# power.net
KiCad netlist of a schematic drawn in Altium Designer
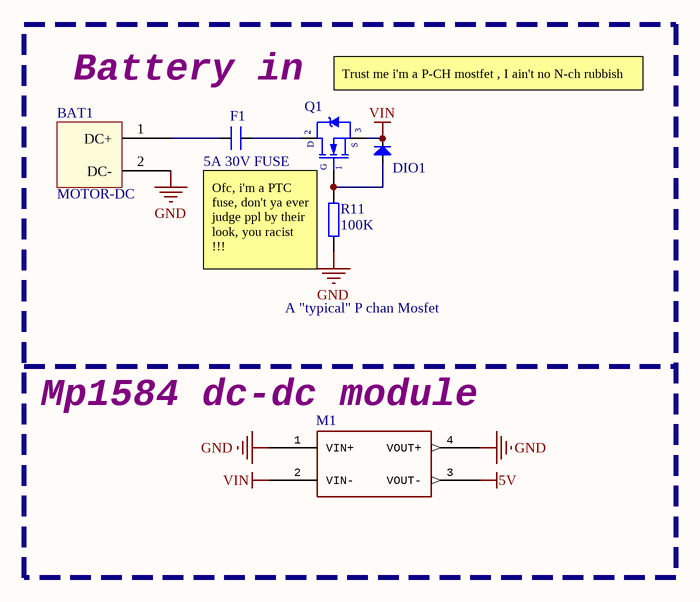
[diagram p0: power.SchDoc]

(export (version "E")
  (design (tool "Eeschema 10.0.6"))
  (components
    (comp (ref "BAT1")
      (value "MOTOR-DC")
      (footprint "CON2-5.08DC")
      (libsource (lib "RASHBERRY_EXTERN") (part "MOTOR-DC"))
    )
    (comp (ref "DIO1")
      (value "Diode SMD")
      (footprint "DIO-SMD-123")
      (description "Default Diode")
      (fields (field (name "PUBLISHER") "Altium Limited"))
      (libsource (lib "My Library") (part "Diode SMD"))
    )
    (comp (ref "F1")
      (value "5A 30V FUSE")
      (footprint "CN2")
      (description "Cap np 104 => 105pF")
      (libsource (lib "My Library") (part "CN2"))
    )
    (comp (ref "M1")
      (value "MP1584-dc-brick-pcb Step down Input: 4.5V - 28V Ouput 0.8V - 25V max. 3A Cheap on ebay")
      (footprint "DC-BRICK")
      (libsource (lib "MP1584-dc-brick") (part "MP1584"))
    )
    (comp (ref "Q1")
      (value "A \"typical\" P chan Mosfet")
      (footprint "QTO-220")
      (description "MOSFET N - CHANNEL 500V - 0.75 - 8A - TO-220")
      (libsource (lib "My Library") (part "IRF840"))
    )
    (comp (ref "R11")
      (value "100K")
      (footprint "SMT0603")
      (description "RES SM 0603 100K")
      (fields (field (name "Comment") "Resistor"))
      (libsource (lib "electronpowered") (part "RES-SM-0603-100K"))
    )
  )
  (nets
    (net (code "1") (name "5V") (class "Default")
      (node (ref "M1") (pin "3") (pinfunction "VOUT-_3") (pintype "output"))
    )
    (net (code "2") (name "GND") (class "Default")
      (node (ref "BAT1") (pin "2") (pinfunction "DC-_2") (pintype "passive"))
      (node (ref "M1") (pin "1") (pinfunction "VIN+_1") (pintype "passive"))
      (node (ref "M1") (pin "4") (pinfunction "VOUT+_4") (pintype "output"))
      (node (ref "R11") (pin "1") (pinfunction "1_1") (pintype "passive"))
    )
    (net (code "3") (name "Net-(BAT1-DC+)") (class "Default")
      (node (ref "BAT1") (pin "1") (pinfunction "DC+_1") (pintype "passive"))
      (node (ref "F1") (pin "1") (pinfunction "1_1") (pintype "passive"))
    )
    (net (code "4") (name "Net-(DIO1-A)") (class "Default")
      (node (ref "DIO1") (pin "1") (pinfunction "A_1") (pintype "passive"))
      (node (ref "Q1") (pin "1") (pinfunction "G_1") (pintype "passive"))
      (node (ref "R11") (pin "2") (pinfunction "2_2") (pintype "passive"))
    )
    (net (code "5") (name "Net-(Q1-D)") (class "Default")
      (node (ref "F1") (pin "2") (pinfunction "2_2") (pintype "passive"))
      (node (ref "Q1") (pin "2") (pinfunction "D_2") (pintype "passive"))
    )
    (net (code "6") (name "VIN") (class "Default")
      (node (ref "DIO1") (pin "2") (pinfunction "K_2") (pintype "passive"))
      (node (ref "M1") (pin "2") (pinfunction "VIN-_2") (pintype "passive"))
      (node (ref "Q1") (pin "3") (pinfunction "S_3") (pintype "passive"))
    )
  )
)
